# 06_Pneumatics.net
KiCad netlist of a schematic drawn in Altium Designer
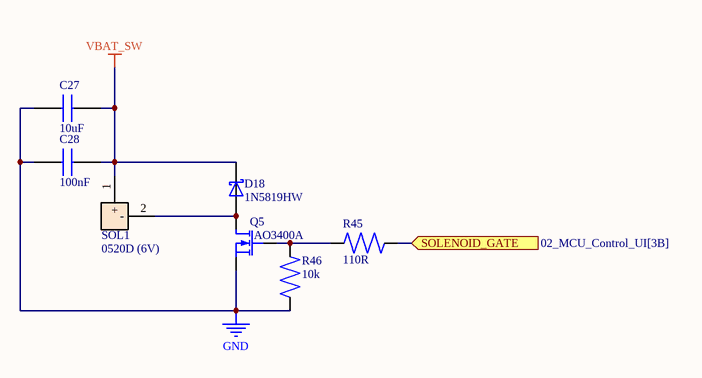
[diagram p0: 06_Pneumatics.SchDoc]

(export (version "E")
  (design (tool "Eeschema 10.0.6"))
  (components
    (comp (ref "C27")
      (value "10uF")
      (footprint "CHIP_0805_SMD")
      (description "Capacitor MLCC, Ceramic, 10 uF, 16 V, ±10%, X7R, SMD 0805, Hitano Enterprise")
      (libsource (lib "Schlib1") (part "CAP_0805_10uF_16V_X7R"))
    )
    (comp (ref "C28")
      (value "100nF")
      (footprint "CHIP_0603_SMD")
      (description "Capacitor MLCC, Ceramic, 100 nF, 50 V, ±10%, X7R, SMD 0603, Samsung Electro-Mechanics")
      (libsource (lib "Schlib1") (part "CAP_0603_100nF_50V_X7R"))
    )
    (comp (ref "D18")
      (value "1N5819HW")
      (footprint "SOD-123_2P_SMD")
      (description "Schottky Barrier Diode, 40V, 1A, Vf=0.45V @ 1A, SOD-123")
      (libsource (lib "Schlib1") (part "DIODE_SCHOTTKY_1N5819HW"))
    )
    (comp (ref "Q5")
      (value "AO3400A")
      (footprint "SOT-23_3P_SMD")
      (libsource (lib "Schlib1") (part "MOSFET_N-CH_AO3400A_SOT23"))
    )
    (comp (ref "R45")
      (value "110R")
      (footprint "CHIP_0805_SMD")
      (libsource (lib "Schlib1") (part "RES_0805_110R_0.1%"))
    )
    (comp (ref "R46")
      (value "10k")
      (footprint "CHIP_0603_SMD")
      (description "Resistor, 10 kOhm, ±1%, 0.1W (1/10W), 75V, SMD 0603, Thick Film, Hitano")
      (libsource (lib "Schlib1") (part "RES_0603_10k_1%"))
    )
    (comp (ref "SOL1")
      (value "0520D (6V)")
      (footprint "PAD_2P_THT_P2.54MM")
      (libsource (lib "Schlib1") (part "ACTUATOR_SOLENOID_0520D_DC6V"))
    )
  )
  (nets
    (net (code "1") (name "/SOLENOID_GATE") (class "Default")
      (node (ref "R45") (pin "2") (pinfunction "2_2") (pintype "passive"))
    )
    (net (code "2") (name "GND") (class "Default")
      (node (ref "C27") (pin "1") (pinfunction "1_1") (pintype "passive"))
      (node (ref "C28") (pin "1") (pinfunction "1_1") (pintype "passive"))
      (node (ref "Q5") (pin "2") (pinfunction "SR_2") (pintype "passive"))
      (node (ref "R46") (pin "1") (pinfunction "1_1") (pintype "passive"))
    )
    (net (code "3") (name "Net-(D18-A)") (class "Default")
      (node (ref "D18") (pin "2") (pinfunction "A_2") (pintype "passive"))
      (node (ref "Q5") (pin "3") (pinfunction "DR_3") (pintype "passive"))
      (node (ref "SOL1") (pin "2") (pinfunction "-_2") (pintype "power_in"))
    )
    (net (code "4") (name "Net-(Q5-G)") (class "Default")
      (node (ref "Q5") (pin "1") (pinfunction "G_1") (pintype "passive"))
      (node (ref "R45") (pin "1") (pinfunction "1_1") (pintype "passive"))
      (node (ref "R46") (pin "2") (pinfunction "2_2") (pintype "passive"))
    )
    (net (code "5") (name "VBAT_SW") (class "Default")
      (node (ref "C27") (pin "2") (pinfunction "2_2") (pintype "passive"))
      (node (ref "C28") (pin "2") (pinfunction "2_2") (pintype "passive"))
      (node (ref "D18") (pin "1") (pinfunction "K_1") (pintype "passive"))
      (node (ref "SOL1") (pin "1") (pinfunction "+_1") (pintype "power_in"))
    )
  )
)
